# blackfin_d_codec.net
KiCad netlist of a schematic drawn in Altium Designer
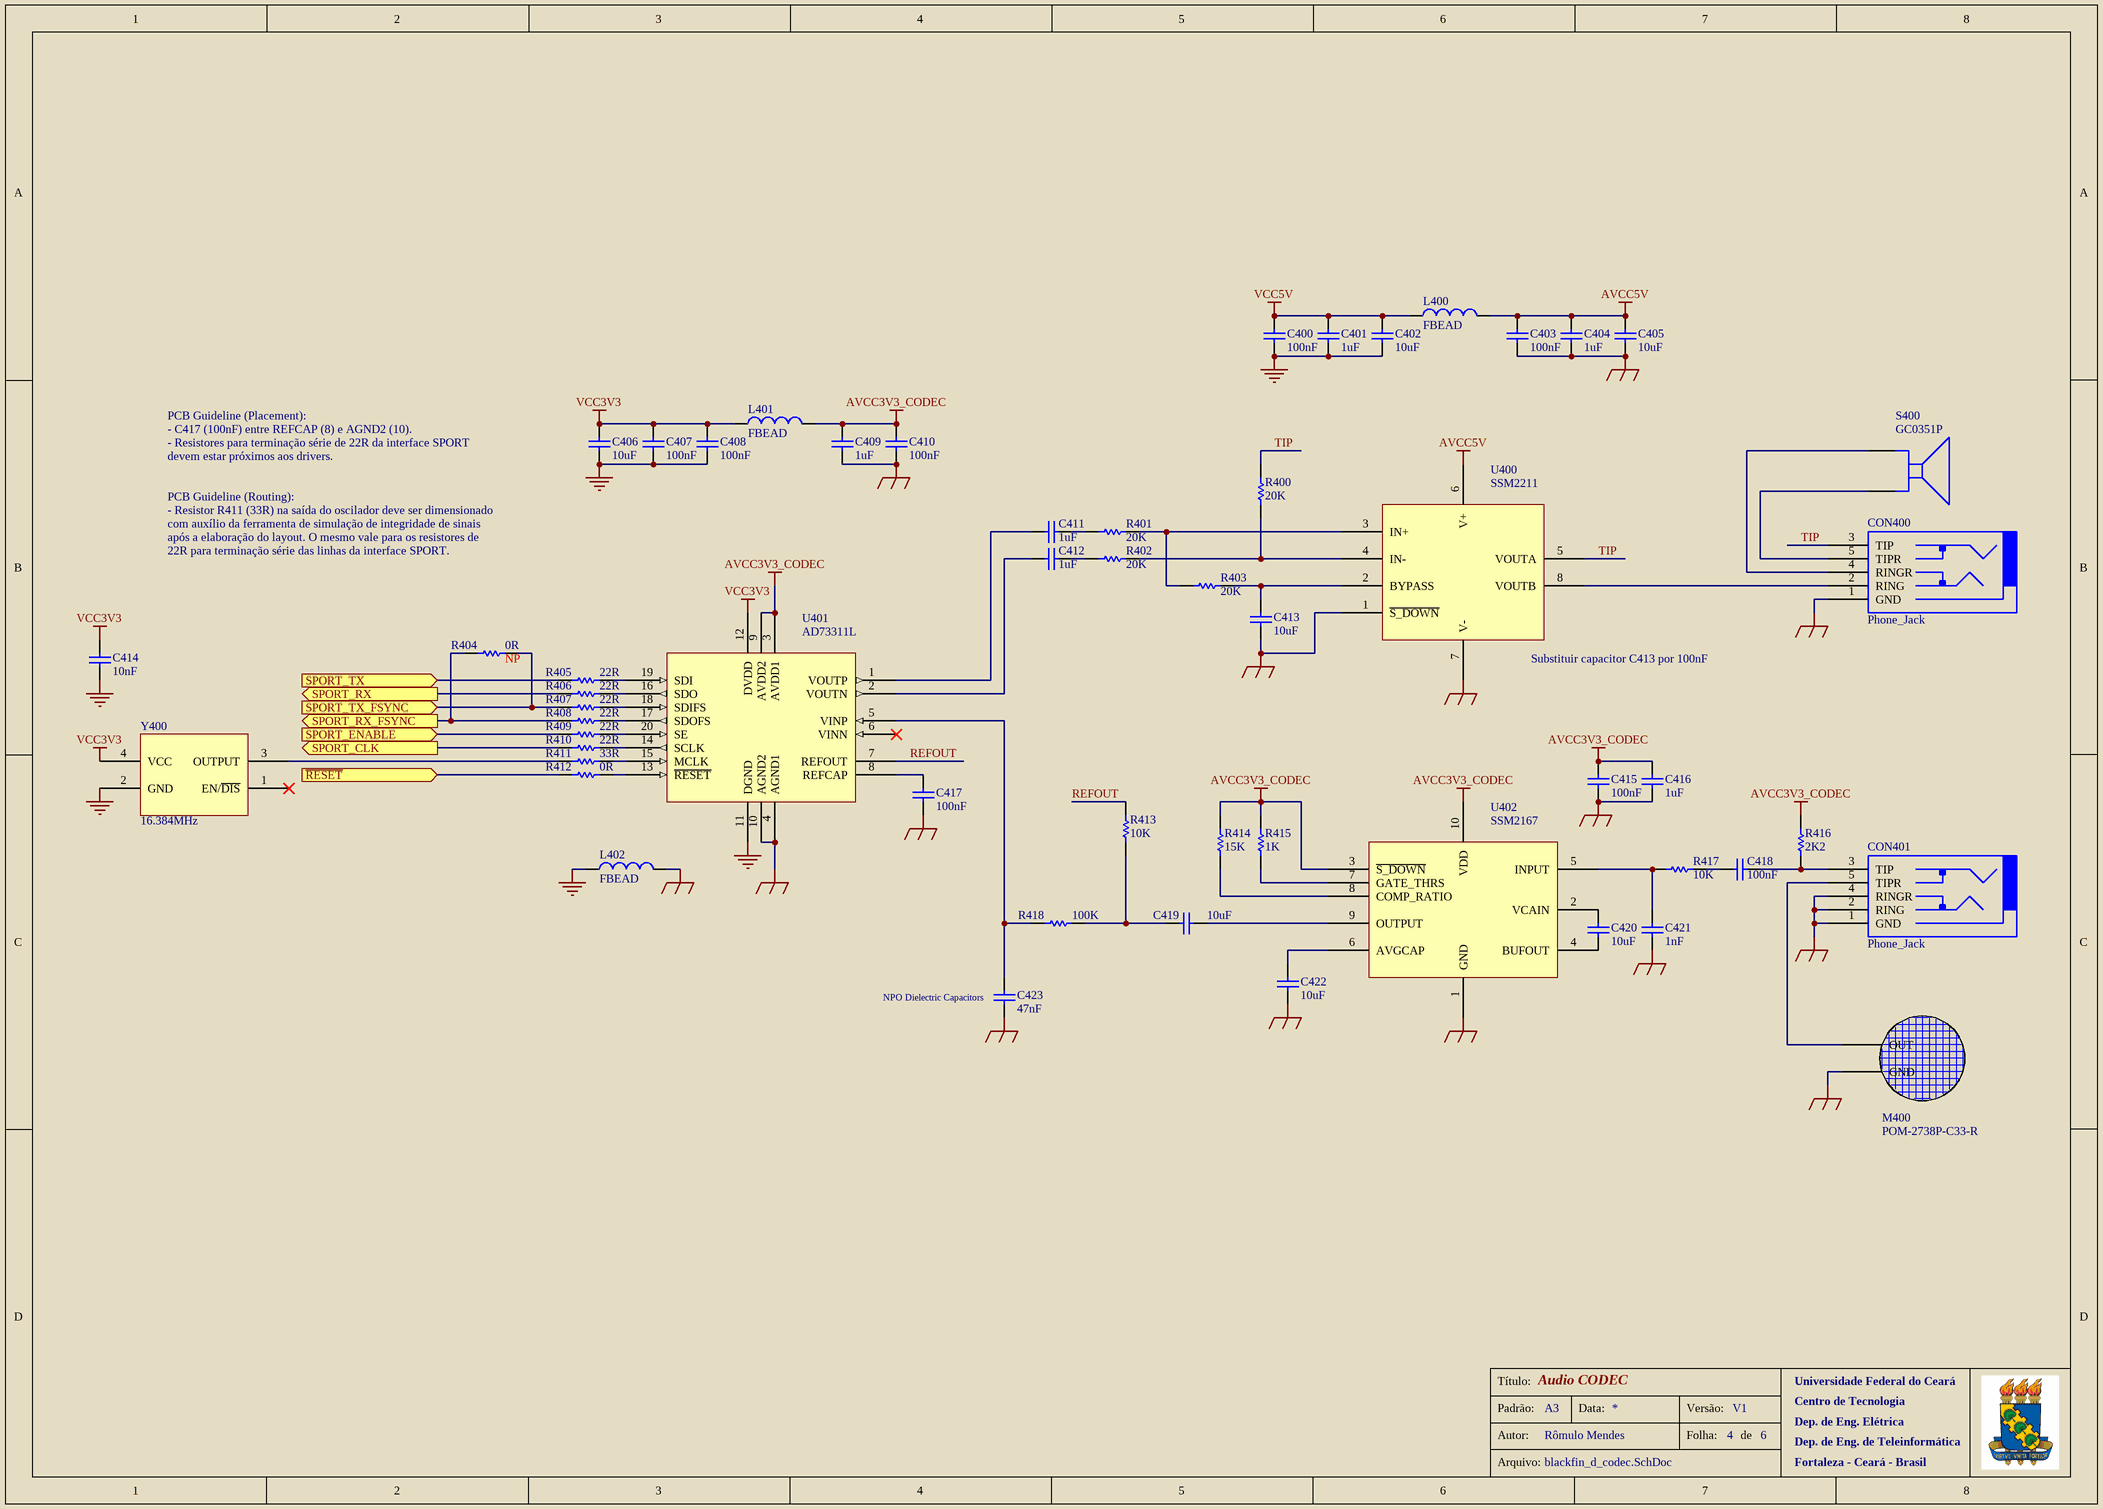
[diagram p0: blackfin_d_codec.SchDoc]

(export (version "E")
  (design (tool "Eeschema 10.0.6"))
  (components
    (comp (ref "C400")
      (value "100nF")
      (footprint "blackfin_pcblib:C_0603")
      (fields
        (field (name "EVENDORPART#") "81-GRM188R71E104KA01")
        (field (name "MANUFACTURER") "Murata")
        (field (name "PART#") "GRM188R71E104KA01J")
      )
      (libsource (lib "blackfin_schlib") (part "Capacitor"))
    )
    (comp (ref "C401")
      (value "1uF")
      (footprint "blackfin_pcblib:C_0603")
      (fields
        (field (name "EVENDORPART#") "81-GRM188F51E105ZA12")
        (field (name "MANUFACTURER") "Murata")
        (field (name "PART#") "GRM188F51E105ZA12D")
      )
      (libsource (lib "blackfin_schlib") (part "Capacitor"))
    )
    (comp (ref "C402")
      (value "10uF")
      (footprint "blackfin_pcblib:C_0805")
      (fields
        (field (name "EVENDORPART#") "810-C2012Y5V1C106Z")
        (field (name "MANUFACTURER") "TDK")
        (field (name "PART#") "C2012Y5V1C106Z")
      )
      (libsource (lib "blackfin_schlib") (part "Capacitor"))
    )
    (comp (ref "C403")
      (value "100nF")
      (footprint "blackfin_pcblib:C_0603")
      (fields
        (field (name "EVENDORPART#") "81-GRM188R71E104KA01")
        (field (name "MANUFACTURER") "Murata")
        (field (name "PART#") "GRM188R71E104KA01J")
      )
      (libsource (lib "blackfin_schlib") (part "Capacitor"))
    )
    (comp (ref "C404")
      (value "1uF")
      (footprint "blackfin_pcblib:C_0603")
      (fields
        (field (name "EVENDORPART#") "81-GRM188F51E105ZA12")
        (field (name "MANUFACTURER") "Murata")
        (field (name "PART#") "GRM188F51E105ZA12D")
      )
      (libsource (lib "blackfin_schlib") (part "Capacitor"))
    )
    (comp (ref "C405")
      (value "10uF")
      (footprint "blackfin_pcblib:C_0805")
      (fields
        (field (name "EVENDORPART#") "810-C2012Y5V1C106Z")
        (field (name "MANUFACTURER") "TDK")
        (field (name "PART#") "C2012Y5V1C106Z")
      )
      (libsource (lib "blackfin_schlib") (part "Capacitor"))
    )
    (comp (ref "C406")
      (value "10uF")
      (footprint "blackfin_pcblib:C_0805")
      (fields
        (field (name "EVENDORPART#") "810-C2012Y5V1C106Z")
        (field (name "MANUFACTURER") "TDK")
        (field (name "PART#") "C2012Y5V1C106Z")
      )
      (libsource (lib "blackfin_schlib") (part "Capacitor"))
    )
    (comp (ref "C407")
      (value "100nF")
      (footprint "blackfin_pcblib:C_0603")
      (fields
        (field (name "EVENDORPART#") "81-GRM188R71E104KA01")
        (field (name "MANUFACTURER") "Murata")
        (field (name "PART#") "GRM188R71E104KA01J")
      )
      (libsource (lib "blackfin_schlib") (part "Capacitor"))
    )
    (comp (ref "C408")
      (value "100nF")
      (footprint "blackfin_pcblib:C_0603")
      (fields
        (field (name "EVENDORPART#") "81-GRM188R71E104KA01")
        (field (name "MANUFACTURER") "Murata")
        (field (name "PART#") "GRM188R71E104KA01J")
      )
      (libsource (lib "blackfin_schlib") (part "Capacitor"))
    )
    (comp (ref "C409")
      (value "1uF")
      (footprint "blackfin_pcblib:C_0603")
      (fields
        (field (name "EVENDORPART#") "81-GRM188F51E105ZA12")
        (field (name "MANUFACTURER") "Murata")
        (field (name "PART#") "GRM188F51E105ZA12D")
      )
      (libsource (lib "blackfin_schlib") (part "Capacitor"))
    )
    (comp (ref "C410")
      (value "100nF")
      (footprint "blackfin_pcblib:C_0603")
      (fields
        (field (name "EVENDORPART#") "81-GRM188R71E104KA01")
        (field (name "MANUFACTURER") "Murata")
        (field (name "PART#") "GRM188R71E104KA01J")
      )
      (libsource (lib "blackfin_schlib") (part "Capacitor"))
    )
    (comp (ref "C411")
      (value "1uF")
      (footprint "blackfin_pcblib:C_0603")
      (fields
        (field (name "EVENDORPART#") "81-GRM188F51E105ZA12")
        (field (name "MANUFACTURER") "Murata")
        (field (name "PART#") "GRM188F51E105ZA12D")
      )
      (libsource (lib "blackfin_schlib") (part "Capacitor"))
    )
    (comp (ref "C412")
      (value "1uF")
      (footprint "blackfin_pcblib:C_0603")
      (fields
        (field (name "EVENDORPART#") "81-GRM188F51E105ZA12")
        (field (name "MANUFACTURER") "Murata")
        (field (name "PART#") "GRM188F51E105ZA12D")
      )
      (libsource (lib "blackfin_schlib") (part "Capacitor"))
    )
    (comp (ref "C413")
      (value "10uF")
      (footprint "blackfin_pcblib:C_0805")
      (fields
        (field (name "EVENDORPART#") "810-C2012Y5V1C106Z")
        (field (name "MANUFACTURER") "TDK")
        (field (name "PART#") "C2012Y5V1C106Z")
      )
      (libsource (lib "blackfin_schlib") (part "Capacitor"))
    )
    (comp (ref "C414")
      (value "10nF")
      (footprint "blackfin_pcblib:C_0603")
      (fields
        (field (name "EVENDORPART#") "77-VJ0603Y103KXAPBC")
        (field (name "MANUFACTURER") "Vishay/Vitramon")
        (field (name "PART#") "VJ0603Y103KXAPW1BC")
      )
      (libsource (lib "blackfin_schlib") (part "Capacitor"))
    )
    (comp (ref "C415")
      (value "100nF")
      (footprint "blackfin_pcblib:C_0603")
      (fields
        (field (name "EVENDORPART#") "81-GRM188R71E104KA01")
        (field (name "MANUFACTURER") "Murata")
        (field (name "PART#") "GRM188R71E104KA01J")
      )
      (libsource (lib "blackfin_schlib") (part "Capacitor"))
    )
    (comp (ref "C416")
      (value "1uF")
      (footprint "blackfin_pcblib:C_0603")
      (fields
        (field (name "EVENDORPART#") "81-GRM188F51E105ZA12")
        (field (name "MANUFACTURER") "Murata")
        (field (name "PART#") "GRM188F51E105ZA12D")
      )
      (libsource (lib "blackfin_schlib") (part "Capacitor"))
    )
    (comp (ref "C417")
      (value "100nF")
      (footprint "blackfin_pcblib:C_0603")
      (fields
        (field (name "EVENDORPART#") "81-GRM188R71E104KA01")
        (field (name "MANUFACTURER") "Murata")
        (field (name "PART#") "GRM188R71E104KA01J")
      )
      (libsource (lib "blackfin_schlib") (part "Capacitor"))
    )
    (comp (ref "C418")
      (value "100nF")
      (footprint "blackfin_pcblib:C_0603")
      (fields
        (field (name "EVENDORPART#") "81-GRM188R71E104KA01")
        (field (name "MANUFACTURER") "Murata")
        (field (name "PART#") "GRM188R71E104KA01J")
      )
      (libsource (lib "blackfin_schlib") (part "Capacitor"))
    )
    (comp (ref "C419")
      (value "10uF")
      (footprint "blackfin_pcblib:C_0805")
      (fields
        (field (name "EVENDORPART#") "810-C2012Y5V1C106Z")
        (field (name "MANUFACTURER") "TDK")
        (field (name "PART#") "C2012Y5V1C106Z")
      )
      (libsource (lib "blackfin_schlib") (part "Capacitor"))
    )
    (comp (ref "C420")
      (value "10uF")
      (footprint "blackfin_pcblib:C_0805")
      (fields
        (field (name "EVENDORPART#") "810-C2012Y5V1C106Z")
        (field (name "MANUFACTURER") "TDK")
        (field (name "PART#") "C2012Y5V1C106Z")
      )
      (libsource (lib "blackfin_schlib") (part "Capacitor"))
    )
    (comp (ref "C421")
      (value "1nF")
      (footprint "blackfin_pcblib:C_0603")
      (fields
        (field (name "EVENDORPART#") "81-GRM1885C2A102JA01")
        (field (name "MANUFACTURER") "Murata")
        (field (name "PART#") "GRM1885C2A102JA01D")
      )
      (libsource (lib "blackfin_schlib") (part "Capacitor"))
    )
    (comp (ref "C422")
      (value "10uF")
      (footprint "blackfin_pcblib:C_0805")
      (fields
        (field (name "EVENDORPART#") "810-C2012Y5V1C106Z")
        (field (name "MANUFACTURER") "TDK")
        (field (name "PART#") "C2012Y5V1C106Z")
      )
      (libsource (lib "blackfin_schlib") (part "Capacitor"))
    )
    (comp (ref "C423")
      (value "47nF")
      (footprint "blackfin_pcblib:C_0603")
      (fields
        (field (name "EVENDORPART#") "81-GRM188R71H473KA61")
        (field (name "MANUFACTURER") "Murata")
        (field (name "PART#") "GRM188R71H473KA61D")
      )
      (libsource (lib "blackfin_schlib") (part "Capacitor"))
    )
    (comp (ref "CON400")
      (value "Phone_Jack")
      (footprint "blackfin_pcblib:Phone_Jack")
      (fields
        (field (name "EVENDORPART#") "CP1-2535SJCT-ND")
        (field (name "MANUFACTURER") "CUI Inc")
        (field (name "PART#") "SJ1-2535-SMT")
      )
      (libsource (lib "blackfin_schlib") (part "Phone_Jack"))
    )
    (comp (ref "CON401")
      (value "Phone_Jack")
      (footprint "blackfin_pcblib:Phone_Jack")
      (fields
        (field (name "EVENDORPART#") "CP1-2535SJCT-ND")
        (field (name "MANUFACTURER") "CUI Inc")
        (field (name "PART#") "SJ1-2535-SMT")
      )
      (libsource (lib "blackfin_schlib") (part "Phone_Jack"))
    )
    (comp (ref "L400")
      (value "FBEAD")
      (footprint "blackfin_pcblib:L_0603")
      (fields
        (field (name "EVENDORPART#") "875-MI0603L301R-10")
        (field (name "MANUFACTURER") "Laird Technologies")
        (field (name "PART#") "MI0603L301R-10")
      )
      (libsource (lib "blackfin_schlib") (part "Inductor"))
    )
    (comp (ref "L401")
      (value "FBEAD")
      (footprint "blackfin_pcblib:L_0603")
      (fields
        (field (name "EVENDORPART#") "875-MI0603L301R-10")
        (field (name "MANUFACTURER") "Laird Technologies")
        (field (name "PART#") "MI0603L301R-10")
      )
      (libsource (lib "blackfin_schlib") (part "Inductor"))
    )
    (comp (ref "L402")
      (value "FBEAD")
      (footprint "blackfin_pcblib:L_0603")
      (fields
        (field (name "EVENDORPART#") "875-MI0603L301R-10")
        (field (name "MANUFACTURER") "Laird Technologies")
        (field (name "PART#") "MI0603L301R-10")
      )
      (libsource (lib "blackfin_schlib") (part "Inductor"))
    )
    (comp (ref "M400")
      (value "POM-2738P-C33-R")
      (footprint "blackfin_pcblib:Microphone")
      (fields (field (name "EVENDORPART#") "665-POM2738PC33R") (field (name "MANUFACTURER") "PUI Audio"))
      (libsource (lib "blackfin_schlib") (part "Microphone"))
    )
    (comp (ref "R400")
      (value "20K")
      (footprint "blackfin_pcblib:R_0603")
      (fields
        (field (name "EVENDORPART#") "71-CRCW0603J-20K-E3")
        (field (name "PART#") "CRCW060320K0JNEA")
        (field (name "MANUFACTURER") "Vishay/Dale")
      )
      (libsource (lib "blackfin_schlib") (part "Resistor"))
    )
    (comp (ref "R401")
      (value "20K")
      (footprint "blackfin_pcblib:R_0603")
      (fields
        (field (name "EVENDORPART#") "71-CRCW0603J-20K-E3")
        (field (name "PART#") "CRCW060320K0JNEA")
        (field (name "MANUFACTURER") "Vishay/Dale")
      )
      (libsource (lib "blackfin_schlib") (part "Resistor"))
    )
    (comp (ref "R402")
      (value "20K")
      (footprint "blackfin_pcblib:R_0603")
      (fields
        (field (name "EVENDORPART#") "71-CRCW0603J-20K-E3")
        (field (name "PART#") "CRCW060320K0JNEA")
        (field (name "MANUFACTURER") "Vishay/Dale")
      )
      (libsource (lib "blackfin_schlib") (part "Resistor"))
    )
    (comp (ref "R403")
      (value "20K")
      (footprint "blackfin_pcblib:R_0603")
      (fields
        (field (name "EVENDORPART#") "71-CRCW0603J-20K-E3")
        (field (name "PART#") "CRCW060320K0JNEA")
        (field (name "MANUFACTURER") "Vishay/Dale")
      )
      (libsource (lib "blackfin_schlib") (part "Resistor"))
    )
    (comp (ref "R404")
      (value "0R")
      (footprint "blackfin_pcblib:R_0603")
      (fields
        (field (name "EVENDORPART#") "71-CRCW06030000Z0EB")
        (field (name "PART#") "CRCW06030000Z0EB")
        (field (name "MANUFACTURER") "Vishay/Dale")
      )
      (libsource (lib "blackfin_schlib") (part "Resistor"))
    )
    (comp (ref "R405")
      (value "22R")
      (footprint "blackfin_pcblib:R_0402")
      (fields
        (field (name "EVENDORPART#") "71-CRCW0402J-22-E3")
        (field (name "PART#") "CRCW040222R0JNED")
        (field (name "MANUFACTURER") "Vishay/Dale")
      )
      (libsource (lib "blackfin_schlib") (part "Resistor"))
    )
    (comp (ref "R406")
      (value "22R")
      (footprint "blackfin_pcblib:R_0402")
      (fields
        (field (name "EVENDORPART#") "71-CRCW0402J-22-E3")
        (field (name "PART#") "CRCW040222R0JNED")
        (field (name "MANUFACTURER") "Vishay/Dale")
      )
      (libsource (lib "blackfin_schlib") (part "Resistor"))
    )
    (comp (ref "R407")
      (value "22R")
      (footprint "blackfin_pcblib:R_0402")
      (fields
        (field (name "EVENDORPART#") "71-CRCW0402J-22-E3")
        (field (name "PART#") "CRCW040222R0JNED")
        (field (name "MANUFACTURER") "Vishay/Dale")
      )
      (libsource (lib "blackfin_schlib") (part "Resistor"))
    )
    (comp (ref "R408")
      (value "22R")
      (footprint "blackfin_pcblib:R_0402")
      (fields
        (field (name "EVENDORPART#") "71-CRCW0402J-22-E3")
        (field (name "PART#") "CRCW040222R0JNED")
        (field (name "MANUFACTURER") "Vishay/Dale")
      )
      (libsource (lib "blackfin_schlib") (part "Resistor"))
    )
    (comp (ref "R409")
      (value "22R")
      (footprint "blackfin_pcblib:R_0402")
      (fields
        (field (name "EVENDORPART#") "71-CRCW0402J-22-E3")
        (field (name "PART#") "CRCW040222R0JNED")
        (field (name "MANUFACTURER") "Vishay/Dale")
      )
      (libsource (lib "blackfin_schlib") (part "Resistor"))
    )
    (comp (ref "R410")
      (value "22R")
      (footprint "blackfin_pcblib:R_0402")
      (fields
        (field (name "EVENDORPART#") "71-CRCW0402J-22-E3")
        (field (name "PART#") "CRCW040222R0JNED")
        (field (name "MANUFACTURER") "Vishay/Dale")
      )
      (libsource (lib "blackfin_schlib") (part "Resistor"))
    )
    (comp (ref "R411")
      (value "33R")
      (footprint "blackfin_pcblib:R_0402")
      (fields
        (field (name "EVENDORPART#") "71-CRCW0402J-33-E3")
        (field (name "PART#") "CRCW040233R0JNED")
        (field (name "MANUFACTURER") "Vishay/Dale")
      )
      (libsource (lib "blackfin_schlib") (part "Resistor"))
    )
    (comp (ref "R412")
      (value "0R")
      (footprint "blackfin_pcblib:R_0603")
      (fields
        (field (name "EVENDORPART#") "71-CRCW06030000Z0EB")
        (field (name "PART#") "CRCW06030000Z0EB")
        (field (name "MANUFACTURER") "Vishay/Dale")
      )
      (libsource (lib "blackfin_schlib") (part "Resistor"))
    )
    (comp (ref "R413")
      (value "10K")
      (footprint "blackfin_pcblib:R_0603")
      (fields
        (field (name "EVENDORPART#") "71-CRCW0603-10K-E3")
        (field (name "PART#") "CRCW060310K0FKEA")
        (field (name "MANUFACTURER") "Vishay/Dale")
      )
      (libsource (lib "blackfin_schlib") (part "Resistor"))
    )
    (comp (ref "R414")
      (value "15K")
      (footprint "blackfin_pcblib:R_0603")
      (fields
        (field (name "EVENDORPART#") "71-CRCW0603J-15K-E3")
        (field (name "PART#") "CRCW060315K0JNEA")
        (field (name "MANUFACTURER") "Vishay/Dale")
      )
      (libsource (lib "blackfin_schlib") (part "Resistor"))
    )
    (comp (ref "R415")
      (value "1K")
      (footprint "blackfin_pcblib:R_0603")
      (fields
        (field (name "EVENDORPART#") "71-CRCW06031K00JNEB")
        (field (name "PART#") "CRCW06031K00JNEB")
        (field (name "MANUFACTURER") "Vishay/Dale")
      )
      (libsource (lib "blackfin_schlib") (part "Resistor"))
    )
    (comp (ref "R416")
      (value "2K2")
      (footprint "blackfin_pcblib:R_0603")
      (fields
        (field (name "EVENDORPART#") "71-CRCW06032K20JNEB")
        (field (name "PART#") "CRCW06032K20JNEB")
        (field (name "MANUFACTURER") "Vishay/Dale")
      )
      (libsource (lib "blackfin_schlib") (part "Resistor"))
    )
    (comp (ref "R417")
      (value "10K")
      (footprint "blackfin_pcblib:R_0603")
      (fields
        (field (name "EVENDORPART#") "71-CRCW0603-10K-E3")
        (field (name "PART#") "CRCW060310K0FKEA")
        (field (name "MANUFACTURER") "Vishay/Dale")
      )
      (libsource (lib "blackfin_schlib") (part "Resistor"))
    )
    (comp (ref "R418")
      (value "100K")
      (footprint "blackfin_pcblib:R_0603")
      (fields
        (field (name "EVENDORPART#") "71-CRCW0603J-100K-E3")
        (field (name "PART#") "CRCW0603100KJNEA")
        (field (name "MANUFACTURER") "Vishay/Dale")
      )
      (libsource (lib "blackfin_schlib") (part "Resistor"))
    )
    (comp (ref "S400")
      (value "GC0351P")
      (footprint "blackfin_pcblib:Speaker")
      (fields
        (field (name "EVENDORPART#") "GC0351P-3-ND")
        (field (name "PART#") "GC0351P-3")
        (field (name "MANUFACTURER") "CUI Inc")
      )
      (libsource (lib "blackfin_schlib") (part "Speaker"))
    )
    (comp (ref "U400")
      (value "SSM2211")
      (footprint "blackfin_pcblib:SOIC-8 (SSM2211)")
      (fields
        (field (name "EVENDORPART#") "SSM2211SZ-ND")
        (field (name "PART#") "SSM2211SZ")
        (field (name "MANUFACTURER") "Analog Devices")
      )
      (libsource (lib "blackfin_schlib") (part "SSM2211"))
    )
    (comp (ref "U401")
      (value "AD73311L")
      (footprint "blackfin_pcblib:TSSOP-20")
      (fields (field (name "EVENDORPART#") "AD73311LARUZ") (field (name "MANUFACTURER") "Analog Devices"))
      (libsource (lib "blackfin_schlib") (part "AD73311L"))
    )
    (comp (ref "U402")
      (value "SSM2167")
      (footprint "blackfin_pcblib:MSOP-10")
      (fields
        (field (name "EVENDORPART#") "SSM2167-1RMZ-REELCT-ND")
        (field (name "MANUFACTURER") "Analog Devices")
        (field (name "PART#") "SSM2167-1RMZ-REEL")
      )
      (libsource (lib "blackfin_schlib") (part "SSM2167"))
    )
    (comp (ref "Y400")
      (value "16.384MHz")
      (footprint "blackfin_pcblib:OSC_16.384MHz")
      (fields
        (field (name "EVENDORPART#") "695-CSX750FBC-163")
        (field (name "PART#") "CSX750FBC-16.384M-UT")
        (field (name "MANUFACTURER") "Citizen")
      )
      (libsource (lib "blackfin_schlib") (part "Oscillator_16.384MHz"))
    )
  )
  (nets
    (net (code "1") (name "/REFOUT") (class "Default")
      (node (ref "R413") (pin "2") (pinfunction "2_2") (pintype "passive"))
      (node (ref "U401") (pin "7") (pinfunction "REFOUT_7") (pintype "power_in"))
    )
    (net (code "2") (name "/SPORT_CLK") (class "Default")
      (node (ref "R410") (pin "1") (pinfunction "1_1") (pintype "passive"))
    )
    (net (code "3") (name "/SPORT_ENABLE") (class "Default")
      (node (ref "R409") (pin "1") (pinfunction "1_1") (pintype "passive"))
    )
    (net (code "4") (name "/SPORT_RX") (class "Default")
      (node (ref "R406") (pin "1") (pinfunction "1_1") (pintype "passive"))
    )
    (net (code "5") (name "/SPORT_RX_FSYNC") (class "Default")
      (node (ref "R404") (pin "1") (pinfunction "1_1") (pintype "passive"))
      (node (ref "R408") (pin "1") (pinfunction "1_1") (pintype "passive"))
    )
    (net (code "6") (name "/SPORT_TX") (class "Default")
      (node (ref "R405") (pin "1") (pinfunction "1_1") (pintype "passive"))
    )
    (net (code "7") (name "/SPORT_TX_FSYNC") (class "Default")
      (node (ref "R404") (pin "2") (pinfunction "2_2") (pintype "passive"))
      (node (ref "R407") (pin "1") (pinfunction "1_1") (pintype "passive"))
    )
    (net (code "8") (name "/TIP") (class "Default")
      (node (ref "CON400") (pin "3") (pinfunction "TIP_3") (pintype "passive"))
      (node (ref "R400") (pin "2") (pinfunction "2_2") (pintype "passive"))
      (node (ref "U400") (pin "5") (pinfunction "VOUTA_5") (pintype "passive"))
    )
    (net (code "9") (name "/~{RESET}") (class "Default")
      (node (ref "R412") (pin "1") (pinfunction "1_1") (pintype "passive"))
    )
    (net (code "10") (name "AVCC3V3_CODEC") (class "Default")
      (node (ref "C409") (pin "2") (pinfunction "2_2") (pintype "passive"))
      (node (ref "C410") (pin "2") (pinfunction "2_2") (pintype "passive"))
      (node (ref "C415") (pin "2") (pinfunction "2_2") (pintype "passive"))
      (node (ref "C416") (pin "2") (pinfunction "2_2") (pintype "passive"))
      (node (ref "L401") (pin "2") (pinfunction "2_2") (pintype "passive"))
      (node (ref "R414") (pin "2") (pinfunction "2_2") (pintype "passive"))
      (node (ref "R415") (pin "2") (pinfunction "2_2") (pintype "passive"))
      (node (ref "R416") (pin "1") (pinfunction "1_1") (pintype "passive"))
      (node (ref "U401") (pin "3") (pinfunction "AVDD1_3") (pintype "power_in"))
      (node (ref "U401") (pin "9") (pinfunction "AVDD2_9") (pintype "power_in"))
      (node (ref "U402") (pin "10") (pinfunction "VDD_10") (pintype "passive"))
      (node (ref "U402") (pin "3") (pinfunction "~{S_DOWN}_3") (pintype "passive"))
    )
    (net (code "11") (name "AVCC5V") (class "Default")
      (node (ref "C403") (pin "2") (pinfunction "2_2") (pintype "passive"))
      (node (ref "C404") (pin "2") (pinfunction "2_2") (pintype "passive"))
      (node (ref "C405") (pin "2") (pinfunction "2_2") (pintype "passive"))
      (node (ref "L400") (pin "2") (pinfunction "2_2") (pintype "passive"))
      (node (ref "U400") (pin "6") (pinfunction "V+_6") (pintype "passive"))
    )
    (net (code "12") (name "EARTH") (class "Default")
      (node (ref "C403") (pin "1") (pinfunction "1_1") (pintype "passive"))
      (node (ref "C404") (pin "1") (pinfunction "1_1") (pintype "passive"))
      (node (ref "C405") (pin "1") (pinfunction "1_1") (pintype "passive"))
      (node (ref "C409") (pin "1") (pinfunction "1_1") (pintype "passive"))
      (node (ref "C410") (pin "1") (pinfunction "1_1") (pintype "passive"))
      (node (ref "C413") (pin "2") (pinfunction "2_2") (pintype "passive"))
      (node (ref "C415") (pin "1") (pinfunction "1_1") (pintype "passive"))
      (node (ref "C416") (pin "1") (pinfunction "1_1") (pintype "passive"))
      (node (ref "C417") (pin "1") (pinfunction "1_1") (pintype "passive"))
      (node (ref "C421") (pin "1") (pinfunction "1_1") (pintype "passive"))
      (node (ref "C422") (pin "2") (pinfunction "2_2") (pintype "passive"))
      (node (ref "C423") (pin "1") (pinfunction "1_1") (pintype "passive"))
      (node (ref "CON400") (pin "1") (pinfunction "GND_1") (pintype "passive"))
      (node (ref "CON401") (pin "1") (pinfunction "GND_1") (pintype "passive"))
      (node (ref "CON401") (pin "2") (pinfunction "RING_2") (pintype "passive"))
      (node (ref "CON401") (pin "4") (pinfunction "RINGR_4") (pintype "passive"))
      (node (ref "L402") (pin "2") (pinfunction "2_2") (pintype "passive"))
      (node (ref "M400") (pin "2") (pinfunction "GND_2") (pintype "passive"))
      (node (ref "U400") (pin "1") (pinfunction "~{S_DOWN}_1") (pintype "passive"))
      (node (ref "U400") (pin "7") (pinfunction "V-_7") (pintype "passive"))
      (node (ref "U401") (pin "10") (pinfunction "AGND2_10") (pintype "power_in"))
      (node (ref "U401") (pin "4") (pinfunction "AGND1_4") (pintype "power_in"))
      (node (ref "U402") (pin "1") (pinfunction "GND_1") (pintype "passive"))
    )
    (net (code "13") (name "GND") (class "Default")
      (node (ref "C400") (pin "1") (pinfunction "1_1") (pintype "passive"))
      (node (ref "C401") (pin "1") (pinfunction "1_1") (pintype "passive"))
      (node (ref "C402") (pin "1") (pinfunction "1_1") (pintype "passive"))
      (node (ref "C406") (pin "1") (pinfunction "1_1") (pintype "passive"))
      (node (ref "C407") (pin "1") (pinfunction "1_1") (pintype "passive"))
      (node (ref "C408") (pin "1") (pinfunction "1_1") (pintype "passive"))
      (node (ref "C414") (pin "1") (pinfunction "1_1") (pintype "passive"))
      (node (ref "L402") (pin "1") (pinfunction "1_1") (pintype "passive"))
      (node (ref "U401") (pin "11") (pinfunction "DGND_11") (pintype "power_in"))
      (node (ref "Y400") (pin "2") (pinfunction "GND_2") (pintype "passive"))
    )
    (net (code "14") (name "Net-(C411-Pad1)") (class "Default")
      (node (ref "C411") (pin "1") (pinfunction "1_1") (pintype "passive"))
      (node (ref "R401") (pin "2") (pinfunction "2_2") (pintype "passive"))
    )
    (net (code "15") (name "Net-(C412-Pad1)") (class "Default")
      (node (ref "C412") (pin "1") (pinfunction "1_1") (pintype "passive"))
      (node (ref "R402") (pin "2") (pinfunction "2_2") (pintype "passive"))
    )
    (net (code "16") (name "Net-(C418-Pad2)") (class "Default")
      (node (ref "C418") (pin "2") (pinfunction "2_2") (pintype "passive"))
      (node (ref "R417") (pin "1") (pinfunction "1_1") (pintype "passive"))
    )
    (net (code "17") (name "Net-(C419-Pad2)") (class "Default")
      (node (ref "C419") (pin "2") (pinfunction "2_2") (pintype "passive"))
      (node (ref "R413") (pin "1") (pinfunction "1_1") (pintype "passive"))
      (node (ref "R418") (pin "1") (pinfunction "1_1") (pintype "passive"))
    )
    (net (code "18") (name "Net-(CON400-RING)") (class "Default")
      (node (ref "CON400") (pin "2") (pinfunction "RING_2") (pintype "passive"))
      (node (ref "U400") (pin "8") (pinfunction "VOUTB_8") (pintype "passive"))
    )
    (net (code "19") (name "Net-(CON400-RINGR)") (class "Default")
      (node (ref "CON400") (pin "4") (pinfunction "RINGR_4") (pintype "passive"))
      (node (ref "S400") (pin "1") (pinfunction "CKT1_1") (pintype "passive"))
    )
    (net (code "20") (name "Net-(CON400-TIPR)") (class "Default")
      (node (ref "CON400") (pin "5") (pinfunction "TIPR_5") (pintype "passive"))
      (node (ref "S400") (pin "2") (pinfunction "CKT2_2") (pintype "passive"))
    )
    (net (code "21") (name "Net-(CON401-TIP)") (class "Default")
      (node (ref "C418") (pin "1") (pinfunction "1_1") (pintype "passive"))
      (node (ref "CON401") (pin "3") (pinfunction "TIP_3") (pintype "passive"))
      (node (ref "R416") (pin "2") (pinfunction "2_2") (pintype "passive"))
    )
    (net (code "22") (name "Net-(CON401-TIPR)") (class "Default")
      (node (ref "CON401") (pin "5") (pinfunction "TIPR_5") (pintype "passive"))
      (node (ref "M400") (pin "1") (pinfunction "OUT_1") (pintype "passive"))
    )
    (net (code "23") (name "Net-(U400-BYPASS)") (class "Default")
      (node (ref "C413") (pin "1") (pinfunction "1_1") (pintype "passive"))
      (node (ref "R403") (pin "1") (pinfunction "1_1") (pintype "passive"))
      (node (ref "U400") (pin "2") (pinfunction "BYPASS_2") (pintype "passive"))
    )
    (net (code "24") (name "Net-(U400-IN+)") (class "Default")
      (node (ref "R401") (pin "1") (pinfunction "1_1") (pintype "passive"))
      (node (ref "R403") (pin "2") (pinfunction "2_2") (pintype "passive"))
      (node (ref "U400") (pin "3") (pinfunction "IN+_3") (pintype "passive"))
    )
    (net (code "25") (name "Net-(U400-IN-)") (class "Default")
      (node (ref "R400") (pin "1") (pinfunction "1_1") (pintype "passive"))
      (node (ref "R402") (pin "1") (pinfunction "1_1") (pintype "passive"))
      (node (ref "U400") (pin "4") (pinfunction "IN-_4") (pintype "passive"))
    )
    (net (code "26") (name "Net-(U401-MCLK)") (class "Default")
      (node (ref "R411") (pin "2") (pinfunction "2_2") (pintype "passive"))
      (node (ref "U401") (pin "15") (pinfunction "MCLK_15") (pintype "input"))
    )
    (net (code "27") (name "Net-(U401-REFCAP)") (class "Default")
      (node (ref "C417") (pin "2") (pinfunction "2_2") (pintype "passive"))
      (node (ref "U401") (pin "8") (pinfunction "REFCAP_8") (pintype "power_in"))
    )
    (net (code "28") (name "Net-(U401-SCLK)") (class "Default")
      (node (ref "R410") (pin "2") (pinfunction "2_2") (pintype "passive"))
      (node (ref "U401") (pin "14") (pinfunction "SCLK_14") (pintype "output"))
    )
    (net (code "29") (name "Net-(U401-SDI)") (class "Default")
      (node (ref "R405") (pin "2") (pinfunction "2_2") (pintype "passive"))
      (node (ref "U401") (pin "19") (pinfunction "SDI_19") (pintype "input"))
    )
    (net (code "30") (name "Net-(U401-SDIFS)") (class "Default")
      (node (ref "R407") (pin "2") (pinfunction "2_2") (pintype "passive"))
      (node (ref "U401") (pin "18") (pinfunction "SDIFS_18") (pintype "input"))
    )
    (net (code "31") (name "Net-(U401-SDO)") (class "Default")
      (node (ref "R406") (pin "2") (pinfunction "2_2") (pintype "passive"))
      (node (ref "U401") (pin "16") (pinfunction "SDO_16") (pintype "output"))
    )
    (net (code "32") (name "Net-(U401-SDOFS)") (class "Default")
      (node (ref "R408") (pin "2") (pinfunction "2_2") (pintype "passive"))
      (node (ref "U401") (pin "17") (pinfunction "SDOFS_17") (pintype "output"))
    )
    (net (code "33") (name "Net-(U401-SE)") (class "Default")
      (node (ref "R409") (pin "2") (pinfunction "2_2") (pintype "passive"))
      (node (ref "U401") (pin "20") (pinfunction "SE_20") (pintype "input"))
    )
    (net (code "34") (name "Net-(U401-VINP)") (class "Default")
      (node (ref "C423") (pin "2") (pinfunction "2_2") (pintype "passive"))
      (node (ref "R418") (pin "2") (pinfunction "2_2") (pintype "passive"))
      (node (ref "U401") (pin "5") (pinfunction "VINP_5") (pintype "input"))
    )
    (net (code "35") (name "Net-(U401-VOUTN)") (class "Default")
      (node (ref "C412") (pin "2") (pinfunction "2_2") (pintype "passive"))
      (node (ref "U401") (pin "2") (pinfunction "VOUTN_2") (pintype "output"))
    )
    (net (code "36") (name "Net-(U401-VOUTP)") (class "Default")
      (node (ref "C411") (pin "2") (pinfunction "2_2") (pintype "passive"))
      (node (ref "U401") (pin "1") (pinfunction "VOUTP_1") (pintype "output"))
    )
    (net (code "37") (name "Net-(U401-~{RESET})") (class "Default")
      (node (ref "R412") (pin "2") (pinfunction "2_2") (pintype "passive"))
      (node (ref "U401") (pin "13") (pinfunction "~{RESET}_13") (pintype "input"))
    )
    (net (code "38") (name "Net-(U402-AVGCAP)") (class "Default")
      (node (ref "C422") (pin "1") (pinfunction "1_1") (pintype "passive"))
      (node (ref "U402") (pin "6") (pinfunction "AVGCAP_6") (pintype "passive"))
    )
    (net (code "39") (name "Net-(U402-BUFOUT)") (class "Default")
      (node (ref "C420") (pin "1") (pinfunction "1_1") (pintype "passive"))
      (node (ref "U402") (pin "4") (pinfunction "BUFOUT_4") (pintype "passive"))
    )
    (net (code "40") (name "Net-(U402-COMP_RATIO)") (class "Default")
      (node (ref "R414") (pin "1") (pinfunction "1_1") (pintype "passive"))
      (node (ref "U402") (pin "8") (pinfunction "COMP_RATIO_8") (pintype "passive"))
    )
    (net (code "41") (name "Net-(U402-GATE_THRS)") (class "Default")
      (node (ref "R415") (pin "1") (pinfunction "1_1") (pintype "passive"))
      (node (ref "U402") (pin "7") (pinfunction "GATE_THRS_7") (pintype "passive"))
    )
    (net (code "42") (name "Net-(U402-INPUT)") (class "Default")
      (node (ref "C421") (pin "2") (pinfunction "2_2") (pintype "passive"))
      (node (ref "R417") (pin "2") (pinfunction "2_2") (pintype "passive"))
      (node (ref "U402") (pin "5") (pinfunction "INPUT_5") (pintype "passive"))
    )
    (net (code "43") (name "Net-(U402-OUTPUT)") (class "Default")
      (node (ref "C419") (pin "1") (pinfunction "1_1") (pintype "passive"))
      (node (ref "U402") (pin "9") (pinfunction "OUTPUT_9") (pintype "passive"))
    )
    (net (code "44") (name "Net-(U402-VCAIN)") (class "Default")
      (node (ref "C420") (pin "2") (pinfunction "2_2") (pintype "passive"))
      (node (ref "U402") (pin "2") (pinfunction "VCAIN_2") (pintype "passive"))
    )
    (net (code "45") (name "Net-(Y400-OUTPUT)") (class "Default")
      (node (ref "R411") (pin "1") (pinfunction "1_1") (pintype "passive"))
      (node (ref "Y400") (pin "3") (pinfunction "OUTPUT_3") (pintype "passive"))
    )
    (net (code "46") (name "VCC3V3") (class "Default")
      (node (ref "C406") (pin "2") (pinfunction "2_2") (pintype "passive"))
      (node (ref "C407") (pin "2") (pinfunction "2_2") (pintype "passive"))
      (node (ref "C408") (pin "2") (pinfunction "2_2") (pintype "passive"))
      (node (ref "C414") (pin "2") (pinfunction "2_2") (pintype "passive"))
      (node (ref "L401") (pin "1") (pinfunction "1_1") (pintype "passive"))
      (node (ref "U401") (pin "12") (pinfunction "DVDD_12") (pintype "power_in"))
      (node (ref "Y400") (pin "4") (pinfunction "VCC_4") (pintype "passive"))
    )
    (net (code "47") (name "VCC5V") (class "Default")
      (node (ref "C400") (pin "2") (pinfunction "2_2") (pintype "passive"))
      (node (ref "C401") (pin "2") (pinfunction "2_2") (pintype "passive"))
      (node (ref "C402") (pin "2") (pinfunction "2_2") (pintype "passive"))
      (node (ref "L400") (pin "1") (pinfunction "1_1") (pintype "passive"))
    )
    (net (code "48") (name "unconnected-(U401-VINN-Pad6)") (class "Default")
      (node (ref "U401") (pin "6") (pinfunction "VINN_6") (pintype "input+no_connect"))
    )
    (net (code "49") (name "unconnected-(Y400-EN{slash}~{DIS}-Pad1)") (class "Default")
      (node (ref "Y400") (pin "1") (pinfunction "EN/~{DIS}_1") (pintype "passive+no_connect"))
    )
  )
)
